# Control_PCB_NiclaSense_Open-source.net
KiCad netlist of a schematic drawn in EAGLE
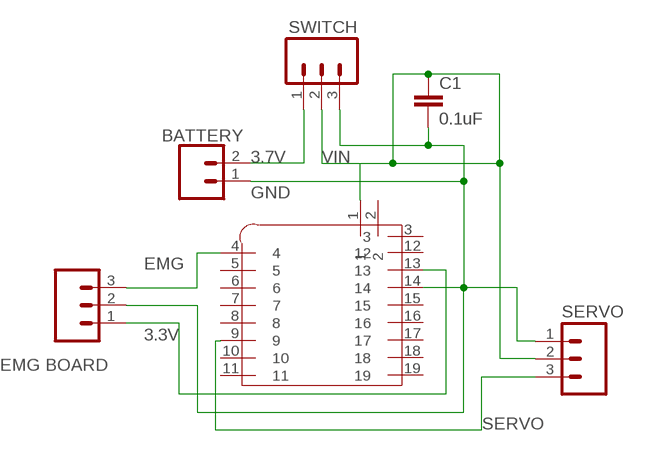
[diagram p0: schematic, sheet 1]

(export (version "E")
  (design (tool "Eeschema 10.0.6"))
  (components
    (comp (ref "BATTERY")
      (value "CONN_02JST-PTH-2")
      (footprint "eagle-import:JST-2-PTH")
      (libsource (lib "eagle-import") (part "CONN_02JST-PTH-2"))
    )
    (comp (ref "C1")
      (value "0.1uF")
      (footprint "eagle-import:C0603K")
      (libsource (lib "eagle-import") (part "C-EUC0603K"))
    )
    (comp (ref "J2")
      (value "455-1750-1-ND")
      (footprint "eagle-import:1X03")
      (libsource (lib "eagle-import") (part "CONN_03"))
    )
    (comp (ref "J3")
      (value "455-1750-1-ND")
      (footprint "eagle-import:1X03")
      (libsource (lib "eagle-import") (part "CONN_03"))
    )
    (comp (ref "SD")
      (value "sadasd")
      (footprint "eagle-import:1X03")
      (libsource (lib "eagle-import") (part "CONN_03"))
    )
    (comp (ref "U$1")
      (value "ARDUINO_NICLA")
      (footprint "eagle-import:ARDUINO_NICLA")
      (libsource (lib "eagle-import") (part "ARDUINO_NICLA"))
    )
  )
  (nets
    (net (code "1") (name "/3.3V") (class "Default")
      (node (ref "SD") (pin "1") (pinfunction "1_1") (pintype "passive"))
      (node (ref "U$1") (pin "13") (pinfunction "13_13") (pintype "bidirectional"))
    )
    (net (code "2") (name "/3.7V") (class "Default")
      (node (ref "BATTERY") (pin "2") (pinfunction "2_2") (pintype "passive"))
      (node (ref "J3") (pin "1") (pinfunction "1_1") (pintype "passive"))
    )
    (net (code "3") (name "/EMG") (class "Default")
      (node (ref "SD") (pin "3") (pinfunction "3_3") (pintype "passive"))
      (node (ref "U$1") (pin "4") (pinfunction "4_4") (pintype "bidirectional"))
    )
    (net (code "4") (name "/GND") (class "Default")
      (node (ref "BATTERY") (pin "1") (pinfunction "1_1") (pintype "passive"))
      (node (ref "C1") (pin "2") (pinfunction "2_2") (pintype "passive"))
      (node (ref "J2") (pin "1") (pinfunction "1_1") (pintype "passive"))
      (node (ref "J3") (pin "3") (pinfunction "3_3") (pintype "passive"))
      (node (ref "SD") (pin "2") (pinfunction "2_2") (pintype "passive"))
      (node (ref "U$1") (pin "14") (pinfunction "14_14") (pintype "bidirectional"))
    )
    (net (code "5") (name "/SERVO") (class "Default")
      (node (ref "J2") (pin "3") (pinfunction "3_3") (pintype "passive"))
      (node (ref "U$1") (pin "9") (pinfunction "9_9") (pintype "bidirectional"))
    )
    (net (code "6") (name "/VIN") (class "Default")
      (node (ref "C1") (pin "1") (pinfunction "1_1") (pintype "passive"))
      (node (ref "J2") (pin "2") (pinfunction "2_2") (pintype "passive"))
      (node (ref "J3") (pin "2") (pinfunction "2_2") (pintype "passive"))
      (node (ref "U$1") (pin "1") (pinfunction "1_1") (pintype "bidirectional"))
    )
    (net (code "7") (name "unconnected-(U$1-Pad2)") (class "Default")
      (node (ref "U$1") (pin "2") (pinfunction "2_2") (pintype "bidirectional"))
    )
    (net (code "8") (name "unconnected-(U$1-Pad3)") (class "Default")
      (node (ref "U$1") (pin "3") (pinfunction "3_3") (pintype "bidirectional"))
    )
    (net (code "9") (name "unconnected-(U$1-Pad5)") (class "Default")
      (node (ref "U$1") (pin "5") (pinfunction "5_5") (pintype "bidirectional"))
    )
    (net (code "10") (name "unconnected-(U$1-Pad6)") (class "Default")
      (node (ref "U$1") (pin "6") (pinfunction "6_6") (pintype "bidirectional"))
    )
    (net (code "11") (name "unconnected-(U$1-Pad7)") (class "Default")
      (node (ref "U$1") (pin "7") (pinfunction "7_7") (pintype "bidirectional"))
    )
    (net (code "12") (name "unconnected-(U$1-Pad8)") (class "Default")
      (node (ref "U$1") (pin "8") (pinfunction "8_8") (pintype "bidirectional"))
    )
    (net (code "13") (name "unconnected-(U$1-Pad10)") (class "Default")
      (node (ref "U$1") (pin "10") (pinfunction "10_10") (pintype "bidirectional"))
    )
    (net (code "14") (name "unconnected-(U$1-Pad11)") (class "Default")
      (node (ref "U$1") (pin "11") (pinfunction "11_11") (pintype "bidirectional"))
    )
    (net (code "15") (name "unconnected-(U$1-Pad12)") (class "Default")
      (node (ref "U$1") (pin "12") (pinfunction "12_12") (pintype "bidirectional"))
    )
    (net (code "16") (name "unconnected-(U$1-Pad15)") (class "Default")
      (node (ref "U$1") (pin "15") (pinfunction "15_15") (pintype "bidirectional"))
    )
    (net (code "17") (name "unconnected-(U$1-Pad16)") (class "Default")
      (node (ref "U$1") (pin "16") (pinfunction "16_16") (pintype "bidirectional"))
    )
    (net (code "18") (name "unconnected-(U$1-Pad17)") (class "Default")
      (node (ref "U$1") (pin "17") (pinfunction "17_17") (pintype "bidirectional"))
    )
    (net (code "19") (name "unconnected-(U$1-Pad18)") (class "Default")
      (node (ref "U$1") (pin "18") (pinfunction "18_18") (pintype "bidirectional"))
    )
    (net (code "20") (name "unconnected-(U$1-Pad19)") (class "Default")
      (node (ref "U$1") (pin "19") (pinfunction "19_19") (pintype "bidirectional"))
    )
  )
)
